# module-mcu.net
KiCad netlist of a schematic drawn in EAGLE
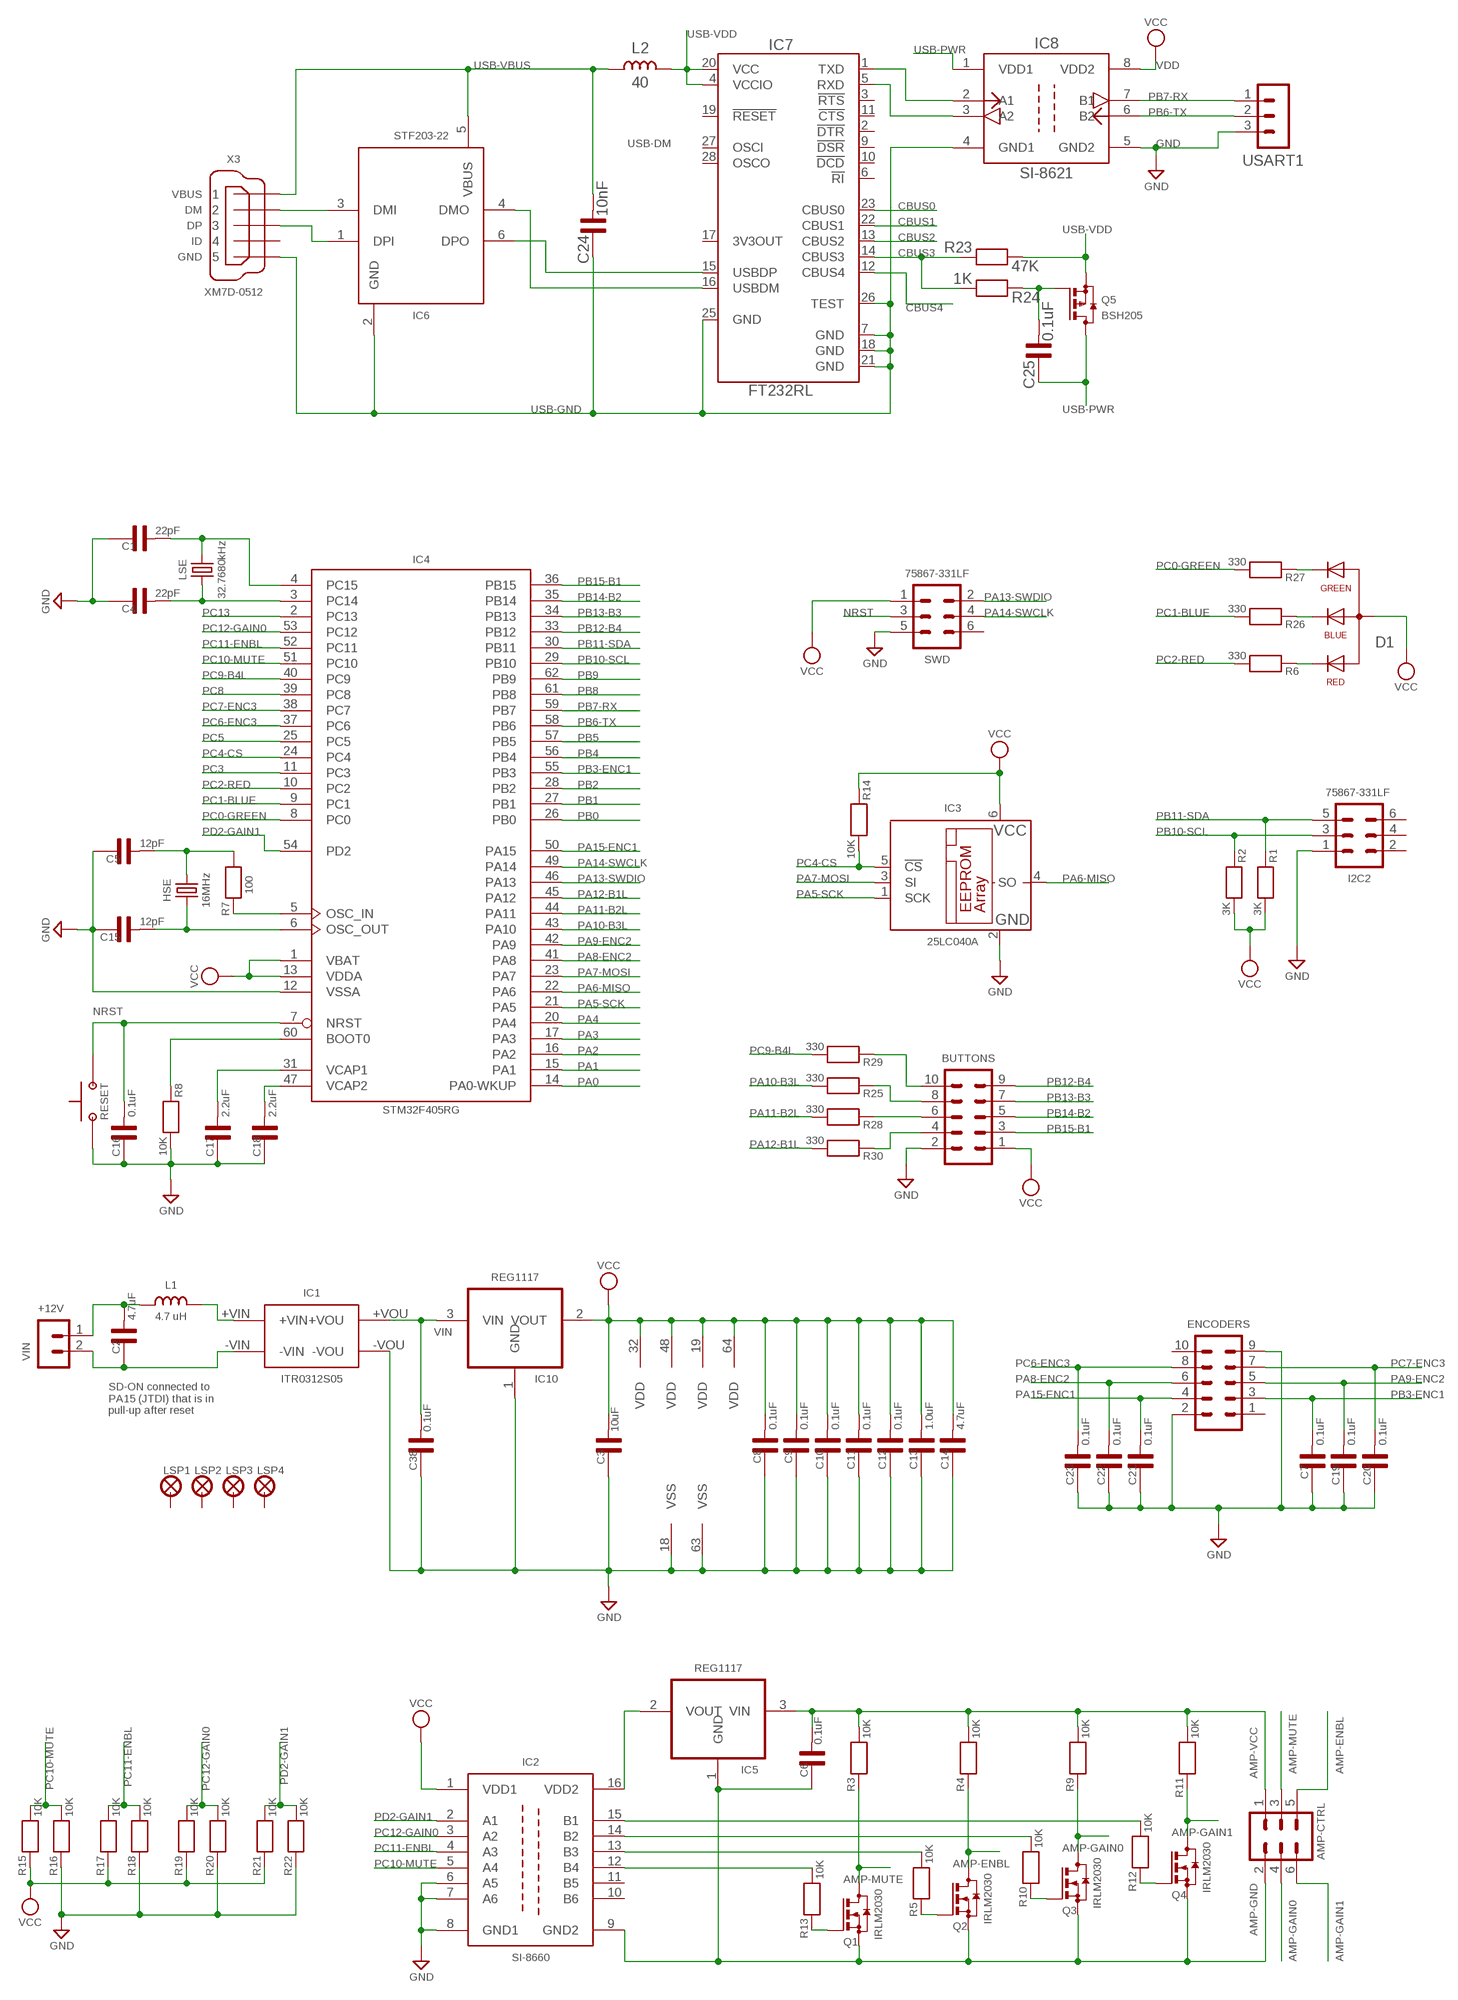
[diagram p0: schematic, sheet 1]

(export (version "E")
  (design (tool "Eeschema 10.0.6"))
  (components
    (comp (ref "AMP-CTRL")
      (value "MA03-2PL")
      (footprint "eagle-import:MA03-2")
      (libsource (lib "eagle-import") (part "MA03-2PL"))
    )
    (comp (ref "BUTTONS")
      (value "MA05-2")
      (footprint "eagle-import:MA05-2")
      (libsource (lib "eagle-import") (part "MA05-2"))
    )
    (comp (ref "C1")
      (value "22pF")
      (footprint "eagle-import:C0805")
      (libsource (lib "eagle-import") (part "C-US0805"))
    )
    (comp (ref "C2")
      (value "4.7uF")
      (footprint "eagle-import:C1206")
      (libsource (lib "eagle-import") (part "C-US1206"))
    )
    (comp (ref "C3")
      (value "10uF")
      (footprint "eagle-import:C0805")
      (libsource (lib "eagle-import") (part "C-US0805"))
    )
    (comp (ref "C4")
      (value "22pF")
      (footprint "eagle-import:C0805")
      (libsource (lib "eagle-import") (part "C-US0805"))
    )
    (comp (ref "C5")
      (value "12pF")
      (footprint "eagle-import:C0805")
      (libsource (lib "eagle-import") (part "C-US0805"))
    )
    (comp (ref "C6")
      (value "0.1uF")
      (footprint "eagle-import:C0805")
      (libsource (lib "eagle-import") (part "C-US0805"))
    )
    (comp (ref "C7")
      (value "0.1uF")
      (footprint "eagle-import:C0805")
      (libsource (lib "eagle-import") (part "C-US0805"))
    )
    (comp (ref "C8")
      (value "0.1uF")
      (footprint "eagle-import:C0805")
      (libsource (lib "eagle-import") (part "C-US0805"))
    )
    (comp (ref "C9")
      (value "0.1uF")
      (footprint "eagle-import:C0805")
      (libsource (lib "eagle-import") (part "C-US0805"))
    )
    (comp (ref "C10")
      (value "0.1uF")
      (footprint "eagle-import:C0805")
      (libsource (lib "eagle-import") (part "C-US0805"))
    )
    (comp (ref "C11")
      (value "0.1uF")
      (footprint "eagle-import:C0805")
      (libsource (lib "eagle-import") (part "C-US0805"))
    )
    (comp (ref "C12")
      (value "0.1uF")
      (footprint "eagle-import:C0805")
      (libsource (lib "eagle-import") (part "C-US0805"))
    )
    (comp (ref "C13")
      (value "1.0uF")
      (footprint "eagle-import:C0805")
      (libsource (lib "eagle-import") (part "C-US0805"))
    )
    (comp (ref "C14")
      (value "4.7uF")
      (footprint "eagle-import:C0805")
      (libsource (lib "eagle-import") (part "C-US0805"))
    )
    (comp (ref "C15")
      (value "12pF")
      (footprint "eagle-import:C0805")
      (libsource (lib "eagle-import") (part "C-US0805"))
    )
    (comp (ref "C16")
      (value "0.1uF")
      (footprint "eagle-import:C0805")
      (libsource (lib "eagle-import") (part "C-US0805"))
    )
    (comp (ref "C17")
      (value "2.2uF")
      (footprint "eagle-import:C0805")
      (libsource (lib "eagle-import") (part "C-US0805"))
    )
    (comp (ref "C18")
      (value "2.2uF")
      (footprint "eagle-import:C0805")
      (libsource (lib "eagle-import") (part "C-US0805"))
    )
    (comp (ref "C19")
      (value "0.1uF")
      (footprint "eagle-import:C0805")
      (libsource (lib "eagle-import") (part "C-US0805"))
    )
    (comp (ref "C20")
      (value "0.1uF")
      (footprint "eagle-import:C0805")
      (libsource (lib "eagle-import") (part "C-US0805"))
    )
    (comp (ref "C21")
      (value "0.1uF")
      (footprint "eagle-import:C0805")
      (libsource (lib "eagle-import") (part "C-US0805"))
    )
    (comp (ref "C22")
      (value "0.1uF")
      (footprint "eagle-import:C0805")
      (libsource (lib "eagle-import") (part "C-US0805"))
    )
    (comp (ref "C23")
      (value "0.1uF")
      (footprint "eagle-import:C0805")
      (libsource (lib "eagle-import") (part "C-US0805"))
    )
    (comp (ref "C24")
      (value "10nF")
      (footprint "eagle-import:C0805")
      (libsource (lib "eagle-import") (part "C-US0805"))
    )
    (comp (ref "C25")
      (value "0.1uF")
      (footprint "eagle-import:C0805")
      (libsource (lib "eagle-import") (part "C-US0805"))
    )
    (comp (ref "C38")
      (value "0.1uF")
      (footprint "eagle-import:C0805")
      (libsource (lib "eagle-import") (part "C-US0805"))
    )
    (comp (ref "D1")
      (value "RGB-LED3X1MM")
      (footprint "eagle-import:RGB-LED-SMD-3X1")
      (libsource (lib "eagle-import") (part "RGB-LED3X1MM"))
    )
    (comp (ref "ENCODERS")
      (value "MA05-2")
      (footprint "eagle-import:MA05-2")
      (libsource (lib "eagle-import") (part "MA05-2"))
    )
    (comp (ref "HSE")
      (value "16MHz")
      (footprint "eagle-import:Q-HC-46X")
      (libsource (lib "eagle-import") (part "Q-HSEHC-46X"))
    )
    (comp (ref "I2C2")
      (value "75867-331LF")
      (footprint "eagle-import:MA03-2")
      (libsource (lib "eagle-import") (part "MA03-2PL"))
    )
    (comp (ref "IC1")
      (value "ITR0312S05")
      (footprint "eagle-import:ITR0312S05")
      (libsource (lib "eagle-import") (part "ITR0312S05"))
    )
    (comp (ref "IC2")
      (value "SI-8660")
      (footprint "eagle-import:SO16")
      (libsource (lib "eagle-import") (part "SI-8660"))
    )
    (comp (ref "IC3")
      (value "25LC040A")
      (footprint "eagle-import:SOT23-6")
      (libsource (lib "eagle-import") (part "25LC040A"))
    )
    (comp (ref "IC4")
      (value "STM32F405RG")
      (footprint "eagle-import:LQFP64")
      (libsource (lib "eagle-import") (part "STM32F405RTG"))
    )
    (comp (ref "IC5")
      (value "REG1117")
      (footprint "eagle-import:SOT223")
      (libsource (lib "eagle-import") (part "REG1117"))
    )
    (comp (ref "IC6")
      (value "STF203-22")
      (footprint "eagle-import:SC70-6")
      (libsource (lib "eagle-import") (part "STF203-22"))
    )
    (comp (ref "IC7")
      (value "FT232RL")
      (footprint "eagle-import:SSOP28")
      (libsource (lib "eagle-import") (part "FT232RL"))
    )
    (comp (ref "IC8")
      (value "SI-8621")
      (footprint "eagle-import:SOIC-8")
      (libsource (lib "eagle-import") (part "SI-8621"))
    )
    (comp (ref "IC10")
      (value "REG1117")
      (footprint "eagle-import:SOT223")
      (libsource (lib "eagle-import") (part "REG1117"))
    )
    (comp (ref "L1")
      (value "4.7 uH")
      (footprint "eagle-import:L0805")
      (libsource (lib "eagle-import") (part "L-USL0805"))
    )
    (comp (ref "L2")
      (value "40")
      (footprint "eagle-import:L0805")
      (libsource (lib "eagle-import") (part "L-USL0805"))
    )
    (comp (ref "LSE")
      (value "32.7680kHz")
      (footprint "eagle-import:Q-CM7V-T1A")
      (libsource (lib "eagle-import") (part "Q-LSECM7V-T1A"))
    )
    (comp (ref "LSP1")
      (value "LSP27")
      (footprint "eagle-import:LSP27")
      (libsource (lib "eagle-import") (part "LSP27"))
    )
    (comp (ref "LSP2")
      (value "LSP27")
      (footprint "eagle-import:LSP27")
      (libsource (lib "eagle-import") (part "LSP27"))
    )
    (comp (ref "LSP3")
      (value "LSP27")
      (footprint "eagle-import:LSP27")
      (libsource (lib "eagle-import") (part "LSP27"))
    )
    (comp (ref "LSP4")
      (value "LSP27")
      (footprint "eagle-import:LSP27")
      (libsource (lib "eagle-import") (part "LSP27"))
    )
    (comp (ref "Q1")
      (value "IRLM2030")
      (footprint "eagle-import:SOT23")
      (libsource (lib "eagle-import") (part "BSS123"))
    )
    (comp (ref "Q2")
      (value "IRLM2030")
      (footprint "eagle-import:SOT23")
      (libsource (lib "eagle-import") (part "BSS123"))
    )
    (comp (ref "Q3")
      (value "IRLM2030")
      (footprint "eagle-import:SOT23")
      (libsource (lib "eagle-import") (part "BSS123"))
    )
    (comp (ref "Q4")
      (value "IRLM2030")
      (footprint "eagle-import:SOT23")
      (libsource (lib "eagle-import") (part "BSS123"))
    )
    (comp (ref "Q5")
      (value "BSH205")
      (footprint "eagle-import:SOT23")
      (libsource (lib "eagle-import") (part "BSH205G2R"))
    )
    (comp (ref "R1")
      (value "3K")
      (footprint "eagle-import:R0805")
      (libsource (lib "eagle-import") (part "R-US0805"))
    )
    (comp (ref "R2")
      (value "3K")
      (footprint "eagle-import:R0805")
      (libsource (lib "eagle-import") (part "R-US0805"))
    )
    (comp (ref "R3")
      (value "10K")
      (footprint "eagle-import:R0805")
      (libsource (lib "eagle-import") (part "R-US0805"))
    )
    (comp (ref "R4")
      (value "10K")
      (footprint "eagle-import:R0805")
      (libsource (lib "eagle-import") (part "R-US0805"))
    )
    (comp (ref "R5")
      (value "10K")
      (footprint "eagle-import:R0805")
      (libsource (lib "eagle-import") (part "R-US0805"))
    )
    (comp (ref "R6")
      (value "330")
      (footprint "eagle-import:R0805")
      (libsource (lib "eagle-import") (part "R-US0805"))
    )
    (comp (ref "R7")
      (value "100")
      (footprint "eagle-import:R0805")
      (libsource (lib "eagle-import") (part "R-US0805"))
    )
    (comp (ref "R8")
      (value "10K")
      (footprint "eagle-import:R0805")
      (libsource (lib "eagle-import") (part "R-US0805"))
    )
    (comp (ref "R9")
      (value "10K")
      (footprint "eagle-import:R0805")
      (libsource (lib "eagle-import") (part "R-US0805"))
    )
    (comp (ref "R10")
      (value "10K")
      (footprint "eagle-import:R0805")
      (libsource (lib "eagle-import") (part "R-US0805"))
    )
    (comp (ref "R11")
      (value "10K")
      (footprint "eagle-import:R0805")
      (libsource (lib "eagle-import") (part "R-US0805"))
    )
    (comp (ref "R12")
      (value "10K")
      (footprint "eagle-import:R0805")
      (libsource (lib "eagle-import") (part "R-US0805"))
    )
    (comp (ref "R13")
      (value "10K")
      (footprint "eagle-import:R0805")
      (libsource (lib "eagle-import") (part "R-US0805"))
    )
    (comp (ref "R14")
      (value "10K")
      (footprint "eagle-import:R0805")
      (libsource (lib "eagle-import") (part "R-US0805"))
    )
    (comp (ref "R15")
      (value "10K")
      (footprint "eagle-import:R0805")
      (libsource (lib "eagle-import") (part "R-US0805"))
    )
    (comp (ref "R16")
      (value "10K")
      (footprint "eagle-import:R0805")
      (libsource (lib "eagle-import") (part "R-US0805"))
    )
    (comp (ref "R17")
      (value "10K")
      (footprint "eagle-import:R0805")
      (libsource (lib "eagle-import") (part "R-US0805"))
    )
    (comp (ref "R18")
      (value "10K")
      (footprint "eagle-import:R0805")
      (libsource (lib "eagle-import") (part "R-US0805"))
    )
    (comp (ref "R19")
      (value "10K")
      (footprint "eagle-import:R0805")
      (libsource (lib "eagle-import") (part "R-US0805"))
    )
    (comp (ref "R20")
      (value "10K")
      (footprint "eagle-import:R0805")
      (libsource (lib "eagle-import") (part "R-US0805"))
    )
    (comp (ref "R21")
      (value "10K")
      (footprint "eagle-import:R0805")
      (libsource (lib "eagle-import") (part "R-US0805"))
    )
    (comp (ref "R22")
      (value "10K")
      (footprint "eagle-import:R0805")
      (libsource (lib "eagle-import") (part "R-US0805"))
    )
    (comp (ref "R23")
      (value "47K")
      (footprint "eagle-import:R0805")
      (libsource (lib "eagle-import") (part "R-US0805"))
    )
    (comp (ref "R24")
      (value "1K")
      (footprint "eagle-import:R0805")
      (libsource (lib "eagle-import") (part "R-US0805"))
    )
    (comp (ref "R25")
      (value "330")
      (footprint "eagle-import:R0805")
      (libsource (lib "eagle-import") (part "R-US0805"))
    )
    (comp (ref "R26")
      (value "330")
      (footprint "eagle-import:R0805")
      (libsource (lib "eagle-import") (part "R-US0805"))
    )
    (comp (ref "R27")
      (value "330")
      (footprint "eagle-import:R0805")
      (libsource (lib "eagle-import") (part "R-US0805"))
    )
    (comp (ref "R28")
      (value "330")
      (footprint "eagle-import:R0805")
      (libsource (lib "eagle-import") (part "R-US0805"))
    )
    (comp (ref "R29")
      (value "330")
      (footprint "eagle-import:R0805")
      (libsource (lib "eagle-import") (part "R-US0805"))
    )
    (comp (ref "R30")
      (value "330")
      (footprint "eagle-import:R0805")
      (libsource (lib "eagle-import") (part "R-US0805"))
    )
    (comp (ref "RESET")
      (value "BUTTON-FSM14JRT")
      (footprint "eagle-import:BUTTON-FSM14JRT")
      (libsource (lib "eagle-import") (part "BUTTON-FSM14JRT"))
    )
    (comp (ref "SWD")
      (value "75867-331LF")
      (footprint "eagle-import:MA03-2-BLUE")
      (libsource (lib "eagle-import") (part "MA03-2BLUE"))
    )
    (comp (ref "USART1")
      (value "MA03-1PL")
      (footprint "eagle-import:MA03-1")
      (libsource (lib "eagle-import") (part "MA03-1PL"))
    )
    (comp (ref "VIN")
      (value "MA02-1GREEN")
      (footprint "eagle-import:MA02-1-GREEN")
      (libsource (lib "eagle-import") (part "MA02-1GREEN"))
    )
    (comp (ref "X3")
      (value "XM7D-0512")
      (footprint "eagle-import:XM7D-0512")
      (libsource (lib "eagle-import") (part "MINI-USB-5-DPI"))
    )
  )
  (nets
    (net (code "2") (name "/AMP-ENBL") (class "Default")
      (node (ref "AMP-CTRL") (pin "5") (pinfunction "5_5") (pintype "passive"))
      (node (ref "Q2") (pin "3") (pinfunction "D_3") (pintype "passive"))
      (node (ref "R4") (pin "1") (pinfunction "1_1") (pintype "passive"))
    )
    (net (code "3") (name "/AMP-GAIN0") (class "Default")
      (node (ref "AMP-CTRL") (pin "4") (pinfunction "4_4") (pintype "passive"))
      (node (ref "Q3") (pin "3") (pinfunction "D_3") (pintype "passive"))
      (node (ref "R9") (pin "1") (pinfunction "1_1") (pintype "passive"))
    )
    (net (code "4") (name "/AMP-GAIN1") (class "Default")
      (node (ref "AMP-CTRL") (pin "6") (pinfunction "6_6") (pintype "passive"))
      (node (ref "Q4") (pin "3") (pinfunction "D_3") (pintype "passive"))
      (node (ref "R11") (pin "1") (pinfunction "1_1") (pintype "passive"))
    )
    (net (code "5") (name "/AMP-GND") (class "Default")
      (node (ref "AMP-CTRL") (pin "2") (pinfunction "2_2") (pintype "passive"))
      (node (ref "C6") (pin "1") (pinfunction "1_1") (pintype "passive"))
      (node (ref "IC2") (pin "9") (pinfunction "GND2_9") (pintype "bidirectional"))
      (node (ref "IC5") (pin "1") (pinfunction "GND_1") (pintype "power_in"))
      (node (ref "Q1") (pin "2") (pinfunction "S_2") (pintype "passive"))
      (node (ref "Q2") (pin "2") (pinfunction "S_2") (pintype "passive"))
      (node (ref "Q3") (pin "2") (pinfunction "S_2") (pintype "passive"))
      (node (ref "Q4") (pin "2") (pinfunction "S_2") (pintype "passive"))
    )
    (net (code "6") (name "/AMP-MUTE") (class "Default")
      (node (ref "AMP-CTRL") (pin "3") (pinfunction "3_3") (pintype "passive"))
      (node (ref "Q1") (pin "3") (pinfunction "D_3") (pintype "passive"))
      (node (ref "R3") (pin "1") (pinfunction "1_1") (pintype "passive"))
    )
    (net (code "7") (name "/AMP-VCC") (class "Default")
      (node (ref "AMP-CTRL") (pin "1") (pinfunction "1_1") (pintype "passive"))
      (node (ref "C6") (pin "2") (pinfunction "2_2") (pintype "passive"))
      (node (ref "IC5") (pin "3") (pinfunction "VIN_3") (pintype "input"))
      (node (ref "R11") (pin "2") (pinfunction "2_2") (pintype "passive"))
      (node (ref "R3") (pin "2") (pinfunction "2_2") (pintype "passive"))
      (node (ref "R4") (pin "2") (pinfunction "2_2") (pintype "passive"))
      (node (ref "R9") (pin "2") (pinfunction "2_2") (pintype "passive"))
    )
    (net (code "8") (name "/CBUS0") (class "Default")
      (node (ref "IC7") (pin "23") (pinfunction "CBUS0_23") (pintype "bidirectional"))
    )
    (net (code "9") (name "/CBUS1") (class "Default")
      (node (ref "IC7") (pin "22") (pinfunction "CBUS1_22") (pintype "bidirectional"))
    )
    (net (code "10") (name "/CBUS2") (class "Default")
      (node (ref "IC7") (pin "13") (pinfunction "CBUS2_13") (pintype "bidirectional"))
    )
    (net (code "11") (name "/CBUS3") (class "Default")
      (node (ref "IC7") (pin "14") (pinfunction "CBUS3_14") (pintype "bidirectional"))
      (node (ref "R23") (pin "1") (pinfunction "1_1") (pintype "passive"))
      (node (ref "R24") (pin "2") (pinfunction "2_2") (pintype "passive"))
    )
    (net (code "12") (name "/CBUS4") (class "Default")
      (node (ref "IC7") (pin "12") (pinfunction "CBUS4_12") (pintype "bidirectional"))
    )
    (net (code "13") (name "/NRST") (class "Default")
      (node (ref "C16") (pin "2") (pinfunction "2_2") (pintype "passive"))
      (node (ref "IC4") (pin "7") (pinfunction "NRST_7") (pintype "bidirectional"))
      (node (ref "RESET") (pin "P$2") (pinfunction "2_P$2") (pintype "bidirectional"))
      (node (ref "SWD") (pin "3") (pinfunction "3_3") (pintype "passive"))
    )
    (net (code "14") (name "/PA0") (class "Default")
      (node (ref "IC4") (pin "14") (pinfunction "PA0-WKUP_14") (pintype "bidirectional"))
    )
    (net (code "15") (name "/PA1") (class "Default")
      (node (ref "IC4") (pin "15") (pinfunction "PA1_15") (pintype "bidirectional"))
    )
    (net (code "16") (name "/PA2") (class "Default")
      (node (ref "IC4") (pin "16") (pinfunction "PA2_16") (pintype "bidirectional"))
    )
    (net (code "17") (name "/PA3") (class "Default")
      (node (ref "IC4") (pin "17") (pinfunction "PA3_17") (pintype "bidirectional"))
    )
    (net (code "18") (name "/PA4") (class "Default")
      (node (ref "IC4") (pin "20") (pinfunction "PA4_20") (pintype "bidirectional"))
    )
    (net (code "19") (name "/PA5-SCK") (class "Default")
      (node (ref "IC3") (pin "1") (pinfunction "SCK_1") (pintype "input"))
      (node (ref "IC4") (pin "21") (pinfunction "PA5_21") (pintype "bidirectional"))
    )
    (net (code "20") (name "/PA6-MISO") (class "Default")
      (node (ref "IC3") (pin "4") (pinfunction "SO_4") (pintype "bidirectional"))
      (node (ref "IC4") (pin "22") (pinfunction "PA6_22") (pintype "bidirectional"))
    )
    (net (code "21") (name "/PA7-MOSI") (class "Default")
      (node (ref "IC3") (pin "3") (pinfunction "SI_3") (pintype "input"))
      (node (ref "IC4") (pin "23") (pinfunction "PA7_23") (pintype "bidirectional"))
    )
    (net (code "22") (name "/PA8-ENC2") (class "Default")
      (node (ref "C22") (pin "2") (pinfunction "2_2") (pintype "passive"))
      (node (ref "ENCODERS") (pin "6") (pinfunction "6_6") (pintype "passive"))
      (node (ref "IC4") (pin "41") (pinfunction "PA8_41") (pintype "bidirectional"))
    )
    (net (code "23") (name "/PA9-ENC2") (class "Default")
      (node (ref "C19") (pin "2") (pinfunction "2_2") (pintype "passive"))
      (node (ref "ENCODERS") (pin "5") (pinfunction "5_5") (pintype "passive"))
      (node (ref "IC4") (pin "42") (pinfunction "PA9_42") (pintype "bidirectional"))
    )
    (net (code "24") (name "/PA10-B3L") (class "Default")
      (node (ref "IC4") (pin "43") (pinfunction "PA10_43") (pintype "bidirectional"))
      (node (ref "R25") (pin "2") (pinfunction "2_2") (pintype "passive"))
    )
    (net (code "25") (name "/PA11-B2L") (class "Default")
      (node (ref "IC4") (pin "44") (pinfunction "PA11_44") (pintype "bidirectional"))
      (node (ref "R28") (pin "2") (pinfunction "2_2") (pintype "passive"))
    )
    (net (code "26") (name "/PA12-B1L") (class "Default")
      (node (ref "IC4") (pin "45") (pinfunction "PA12_45") (pintype "bidirectional"))
      (node (ref "R30") (pin "2") (pinfunction "2_2") (pintype "passive"))
    )
    (net (code "27") (name "/PA13-SWDIO") (class "Default")
      (node (ref "IC4") (pin "46") (pinfunction "PA13_46") (pintype "bidirectional"))
      (node (ref "SWD") (pin "2") (pinfunction "2_2") (pintype "passive"))
    )
    (net (code "28") (name "/PA14-SWCLK") (class "Default")
      (node (ref "IC4") (pin "49") (pinfunction "PA14_49") (pintype "bidirectional"))
      (node (ref "SWD") (pin "4") (pinfunction "4_4") (pintype "passive"))
    )
    (net (code "29") (name "/PA15-ENC1") (class "Default")
      (node (ref "C21") (pin "2") (pinfunction "2_2") (pintype "passive"))
      (node (ref "ENCODERS") (pin "4") (pinfunction "4_4") (pintype "passive"))
      (node (ref "IC4") (pin "50") (pinfunction "PA15_50") (pintype "bidirectional"))
    )
    (net (code "30") (name "/PB0") (class "Default")
      (node (ref "IC4") (pin "26") (pinfunction "PB0_26") (pintype "bidirectional"))
    )
    (net (code "31") (name "/PB1") (class "Default")
      (node (ref "IC4") (pin "27") (pinfunction "PB1_27") (pintype "bidirectional"))
    )
    (net (code "32") (name "/PB2") (class "Default")
      (node (ref "IC4") (pin "28") (pinfunction "PB2_28") (pintype "bidirectional"))
    )
    (net (code "33") (name "/PB3-ENC1") (class "Default")
      (node (ref "C7") (pin "2") (pinfunction "2_2") (pintype "passive"))
      (node (ref "ENCODERS") (pin "3") (pinfunction "3_3") (pintype "passive"))
      (node (ref "IC4") (pin "55") (pinfunction "PB3_55") (pintype "bidirectional"))
    )
    (net (code "34") (name "/PB4") (class "Default")
      (node (ref "IC4") (pin "56") (pinfunction "PB4_56") (pintype "bidirectional"))
    )
    (net (code "35") (name "/PB5") (class "Default")
      (node (ref "IC4") (pin "57") (pinfunction "PB5_57") (pintype "bidirectional"))
    )
    (net (code "36") (name "/PB6-TX") (class "Default")
      (node (ref "IC4") (pin "58") (pinfunction "PB6_58") (pintype "bidirectional"))
      (node (ref "IC8") (pin "6") (pinfunction "B2_6") (pintype "bidirectional"))
      (node (ref "USART1") (pin "2") (pinfunction "2_2") (pintype "passive"))
    )
    (net (code "37") (name "/PB7-RX") (class "Default")
      (node (ref "IC4") (pin "59") (pinfunction "PB7_59") (pintype "bidirectional"))
      (node (ref "IC8") (pin "7") (pinfunction "B1_7") (pintype "bidirectional"))
      (node (ref "USART1") (pin "1") (pinfunction "1_1") (pintype "passive"))
    )
    (net (code "38") (name "/PB8") (class "Default")
      (node (ref "IC4") (pin "61") (pinfunction "PB8_61") (pintype "bidirectional"))
    )
    (net (code "39") (name "/PB9") (class "Default")
      (node (ref "IC4") (pin "62") (pinfunction "PB9_62") (pintype "bidirectional"))
    )
    (net (code "40") (name "/PB10-SCL") (class "Default")
      (node (ref "I2C2") (pin "3") (pinfunction "3_3") (pintype "passive"))
      (node (ref "IC4") (pin "29") (pinfunction "PB10_29") (pintype "bidirectional"))
      (node (ref "R2") (pin "1") (pinfunction "1_1") (pintype "passive"))
    )
    (net (code "41") (name "/PB11-SDA") (class "Default")
      (node (ref "I2C2") (pin "5") (pinfunction "5_5") (pintype "passive"))
      (node (ref "IC4") (pin "30") (pinfunction "PB11_30") (pintype "bidirectional"))
      (node (ref "R1") (pin "1") (pinfunction "1_1") (pintype "passive"))
    )
    (net (code "42") (name "/PB12-B4") (class "Default")
      (node (ref "BUTTONS") (pin "9") (pinfunction "9_9") (pintype "passive"))
      (node (ref "IC4") (pin "33") (pinfunction "PB12_33") (pintype "bidirectional"))
    )
    (net (code "43") (name "/PB13-B3") (class "Default")
      (node (ref "BUTTONS") (pin "7") (pinfunction "7_7") (pintype "passive"))
      (node (ref "IC4") (pin "34") (pinfunction "PB13_34") (pintype "bidirectional"))
    )
    (net (code "44") (name "/PB14-B2") (class "Default")
      (node (ref "BUTTONS") (pin "5") (pinfunction "5_5") (pintype "passive"))
      (node (ref "IC4") (pin "35") (pinfunction "PB14_35") (pintype "bidirectional"))
    )
    (net (code "45") (name "/PB15-B1") (class "Default")
      (node (ref "BUTTONS") (pin "3") (pinfunction "3_3") (pintype "passive"))
      (node (ref "IC4") (pin "36") (pinfunction "PB15_36") (pintype "bidirectional"))
    )
    (net (code "46") (name "/PC0-GREEN") (class "Default")
      (node (ref "IC4") (pin "8") (pinfunction "PC0_8") (pintype "bidirectional"))
      (node (ref "R27") (pin "2") (pinfunction "2_2") (pintype "passive"))
    )
    (net (code "47") (name "/PC1-BLUE") (class "Default")
      (node (ref "IC4") (pin "9") (pinfunction "PC1_9") (pintype "bidirectional"))
      (node (ref "R26") (pin "2") (pinfunction "2_2") (pintype "passive"))
    )
    (net (code "48") (name "/PC2-RED") (class "Default")
      (node (ref "IC4") (pin "10") (pinfunction "PC2_10") (pintype "bidirectional"))
      (node (ref "R6") (pin "2") (pinfunction "2_2") (pintype "passive"))
    )
    (net (code "49") (name "/PC3") (class "Default")
      (node (ref "IC4") (pin "11") (pinfunction "PC3_11") (pintype "bidirectional"))
    )
    (net (code "50") (name "/PC4-CS") (class "Default")
      (node (ref "IC3") (pin "5") (pinfunction "~{CS}_5") (pintype "input"))
      (node (ref "IC4") (pin "24") (pinfunction "PC4_24") (pintype "bidirectional"))
      (node (ref "R14") (pin "2") (pinfunction "2_2") (pintype "passive"))
    )
    (net (code "51") (name "/PC5") (class "Default")
      (node (ref "IC4") (pin "25") (pinfunction "PC5_25") (pintype "bidirectional"))
    )
    (net (code "52") (name "/PC6-ENC3") (class "Default")
      (node (ref "C23") (pin "2") (pinfunction "2_2") (pintype "passive"))
      (node (ref "ENCODERS") (pin "8") (pinfunction "8_8") (pintype "passive"))
      (node (ref "IC4") (pin "37") (pinfunction "PC6_37") (pintype "bidirectional"))
    )
    (net (code "53") (name "/PC7-ENC3") (class "Default")
      (node (ref "C20") (pin "2") (pinfunction "2_2") (pintype "passive"))
      (node (ref "ENCODERS") (pin "7") (pinfunction "7_7") (pintype "passive"))
      (node (ref "IC4") (pin "38") (pinfunction "PC7_38") (pintype "bidirectional"))
    )
    (net (code "54") (name "/PC8") (class "Default")
      (node (ref "IC4") (pin "39") (pinfunction "PC8_39") (pintype "bidirectional"))
    )
    (net (code "55") (name "/PC9-B4L") (class "Default")
      (node (ref "IC4") (pin "40") (pinfunction "PC9_40") (pintype "bidirectional"))
      (node (ref "R29") (pin "2") (pinfunction "2_2") (pintype "passive"))
    )
    (net (code "56") (name "/PC10-MUTE") (class "Default")
      (node (ref "IC2") (pin "5") (pinfunction "A4_5") (pintype "bidirectional"))
      (node (ref "IC4") (pin "51") (pinfunction "PC10_51") (pintype "bidirectional"))
      (node (ref "R15") (pin "2") (pinfunction "2_2") (pintype "passive"))
      (node (ref "R16") (pin "2") (pinfunction "2_2") (pintype "passive"))
    )
    (net (code "57") (name "/PC11-ENBL") (class "Default")
      (node (ref "IC2") (pin "4") (pinfunction "A3_4") (pintype "bidirectional"))
      (node (ref "IC4") (pin "52") (pinfunction "PC11_52") (pintype "bidirectional"))
      (node (ref "R17") (pin "2") (pinfunction "2_2") (pintype "passive"))
      (node (ref "R18") (pin "2") (pinfunction "2_2") (pintype "passive"))
    )
    (net (code "58") (name "/PC12-GAIN0") (class "Default")
      (node (ref "IC2") (pin "3") (pinfunction "A2_3") (pintype "bidirectional"))
      (node (ref "IC4") (pin "53") (pinfunction "PC12_53") (pintype "bidirectional"))
      (node (ref "R19") (pin "2") (pinfunction "2_2") (pintype "passive"))
      (node (ref "R20") (pin "2") (pinfunction "2_2") (pintype "passive"))
    )
    (net (code "59") (name "/PC13") (class "Default")
      (node (ref "IC4") (pin "2") (pinfunction "PC13_2") (pintype "bidirectional"))
    )
    (net (code "60") (name "/PD2-GAIN1") (class "Default")
      (node (ref "IC2") (pin "2") (pinfunction "A1_2") (pintype "bidirectional"))
      (node (ref "IC4") (pin "54") (pinfunction "PD2_54") (pintype "bidirectional"))
      (node (ref "R21") (pin "2") (pinfunction "2_2") (pintype "passive"))
      (node (ref "R22") (pin "2") (pinfunction "2_2") (pintype "passive"))
    )
    (net (code "61") (name "/USB-DM") (class "Default")
      (node (ref "IC6") (pin "4") (pinfunction "DMO_4") (pintype "bidirectional"))
      (node (ref "IC7") (pin "16") (pinfunction "USBDM_16") (pintype "bidirectional"))
    )
    (net (code "62") (name "/USB-GND") (class "Default")
      (node (ref "C24") (pin "1") (pinfunction "1_1") (pintype "passive"))
      (node (ref "IC6") (pin "2") (pinfunction "GND_2") (pintype "bidirectional"))
      (node (ref "IC7") (pin "18") (pinfunction "GND_18") (pintype "power_in"))
      (node (ref "IC7") (pin "21") (pinfunction "GND_21") (pintype "power_in"))
      (node (ref "IC7") (pin "25") (pinfunction "GND_25") (pintype "power_in"))
      (node (ref "IC7") (pin "26") (pinfunction "TEST_26") (pintype "input"))
      (node (ref "IC7") (pin "7") (pinfunction "GND_7") (pintype "power_in"))
      (node (ref "IC8") (pin "4") (pinfunction "GND1_4") (pintype "bidirectional"))
      (node (ref "X3") (pin "5") (pinfunction "5_5") (pintype "passive"))
    )
    (net (code "63") (name "/USB-PWR") (class "Default")
      (node (ref "C25") (pin "1") (pinfunction "1_1") (pintype "passive"))
      (node (ref "IC8") (pin "1") (pinfunction "VDD1_1") (pintype "bidirectional"))
      (node (ref "Q5") (pin "3") (pinfunction "D_3") (pintype "passive"))
    )
    (net (code "64") (name "/USB-VBUS") (class "Default")
      (node (ref "C24") (pin "2") (pinfunction "2_2") (pintype "passive"))
      (node (ref "IC6") (pin "5") (pinfunction "VBUS_5") (pintype "bidirectional"))
      (node (ref "L2") (pin "1") (pinfunction "1_1") (pintype "passive"))
      (node (ref "X3") (pin "1") (pinfunction "1_1") (pintype "passive"))
    )
    (net (code "65") (name "/USB-VDD") (class "Default")
      (node (ref "IC7") (pin "20") (pinfunction "VCC_20") (pintype "power_in"))
      (node (ref "IC7") (pin "4") (pinfunction "VCCIO_4") (pintype "power_in"))
      (node (ref "L2") (pin "2") (pinfunction "2_2") (pintype "passive"))
      (node (ref "Q5") (pin "2") (pinfunction "S_2") (pintype "passive"))
      (node (ref "R23") (pin "2") (pinfunction "2_2") (pintype "passive"))
    )
    (net (code "66") (name "/VIN") (class "Default")
      (node (ref "C38") (pin "2") (pinfunction "2_2") (pintype "passive"))
      (node (ref "IC1") (pin "+VOU") (pinfunction "+VOU_+VOU") (pintype "bidirectional"))
      (node (ref "IC10") (pin "3") (pinfunction "VIN_3") (pintype "input"))
    )
    (net (code "67") (name "GND") (class "Default")
      (node (ref "BUTTONS") (pin "2") (pinfunction "2_2") (pintype "passive"))
      (node (ref "C1") (pin "1") (pinfunction "1_1") (pintype "passive"))
      (node (ref "C10") (pin "1") (pinfunction "1_1") (pintype "passive"))
      (node (ref "C11") (pin "1") (pinfunction "1_1") (pintype "passive"))
      (node (ref "C12") (pin "1") (pinfunction "1_1") (pintype "passive"))
      (node (ref "C13") (pin "1") (pinfunction "1_1") (pintype "passive"))
      (node (ref "C14") (pin "1") (pinfunction "1_1") (pintype "passive"))
      (node (ref "C15") (pin "1") (pinfunction "1_1") (pintype "passive"))
      (node (ref "C16") (pin "1") (pinfunction "1_1") (pintype "passive"))
      (node (ref "C17") (pin "1") (pinfunction "1_1") (pintype "passive"))
      (node (ref "C18") (pin "1") (pinfunction "1_1") (pintype "passive"))
      (node (ref "C19") (pin "1") (pinfunction "1_1") (pintype "passive"))
      (node (ref "C20") (pin "1") (pinfunction "1_1") (pintype "passive"))
      (node (ref "C21") (pin "1") (pinfunction "1_1") (pintype "passive"))
      (node (ref "C22") (pin "1") (pinfunction "1_1") (pintype "passive"))
      (node (ref "C23") (pin "1") (pinfunction "1_1") (pintype "passive"))
      (node (ref "C3") (pin "1") (pinfunction "1_1") (pintype "passive"))
      (node (ref "C38") (pin "1") (pinfunction "1_1") (pintype "passive"))
      (node (ref "C4") (pin "1") (pinfunction "1_1") (pintype "passive"))
      (node (ref "C5") (pin "1") (pinfunction "1_1") (pintype "passive"))
      (node (ref "C7") (pin "1") (pinfunction "1_1") (pintype "passive"))
      (node (ref "C8") (pin "1") (pinfunction "1_1") (pintype "passive"))
      (node (ref "C9") (pin "1") (pinfunction "1_1") (pintype "passive"))
      (node (ref "ENCODERS") (pin "2") (pinfunction "2_2") (pintype "passive"))
      (node (ref "ENCODERS") (pin "9") (pinfunction "9_9") (pintype "passive"))
      (node (ref "I2C2") (pin "1") (pinfunction "1_1") (pintype "passive"))
      (node (ref "IC1") (pin "-VOU") (pinfunction "-VOU_-VOU") (pintype "bidirectional"))
      (node (ref "IC10") (pin "1") (pinfunction "GND_1") (pintype "power_in"))
      (node (ref "IC2") (pin "6") (pinfunction "A5_6") (pintype "bidirectional"))
      (node (ref "IC2") (pin "7") (pinfunction "A6_7") (pintype "bidirectional"))
      (node (ref "IC2") (pin "8") (pinfunction "GND1_8") (pintype "bidirectional"))
      (node (ref "IC3") (pin "2") (pinfunction "GND_2") (pintype "power_in"))
      (node (ref "IC4") (pin "12") (pinfunction "VSSA_12") (pintype "power_in"))
      (node (ref "IC4") (pin "18") (pinfunction "VSS_18") (pintype "power_in"))
      (node (ref "IC4") (pin "63") (pinfunction "VSS_63") (pintype "power_in"))
      (node (ref "IC8") (pin "5") (pinfunction "GND2_5") (pintype "bidirectional"))
      (node (ref "R16") (pin "1") (pinfunction "1_1") (pintype "passive"))
      (node (ref "R18") (pin "1") (pinfunction "1_1") (pintype "passive"))
      (node (ref "R20") (pin "1") (pinfunction "1_1") (pintype "passive"))
      (node (ref "R22") (pin "1") (pinfunction "1_1") (pintype "passive"))
      (node (ref "R8") (pin "2") (pinfunction "2_2") (pintype "passive"))
      (node (ref "RESET") (pin "P$1") (pinfunction "1_P$1") (pintype "bidirectional"))
      (node (ref "SWD") (pin "5") (pinfunction "5_5") (pintype "passive"))
      (node (ref "USART1") (pin "3") (pinfunction "3_3") (pintype "passive"))
    )
    (net (code "68") (name "Net-(BUTTONS-Pad4)") (class "Default")
      (node (ref "BUTTONS") (pin "4") (pinfunction "4_4") (pintype "passive"))
      (node (ref "R30") (pin "1") (pinfunction "1_1") (pintype "passive"))
    )
    (net (code "69") (name "Net-(BUTTONS-Pad6)") (class "Default")
      (node (ref "BUTTONS") (pin "6") (pinfunction "6_6") (pintype "passive"))
      (node (ref "R28") (pin "1") (pinfunction "1_1") (pintype "passive"))
    )
    (net (code "70") (name "Net-(BUTTONS-Pad8)") (class "Default")
      (node (ref "BUTTONS") (pin "8") (pinfunction "8_8") (pintype "passive"))
      (node (ref "R25") (pin "1") (pinfunction "1_1") (pintype "passive"))
    )
    (net (code "71") (name "Net-(BUTTONS-Pad10)") (class "Default")
      (node (ref "BUTTONS") (pin "10") (pinfunction "10_10") (pintype "passive"))
      (node (ref "R29") (pin "1") (pinfunction "1_1") (pintype "passive"))
    )
    (net (code "72") (name "Net-(C2-Pad1)") (class "Default")
      (node (ref "C2") (pin "1") (pinfunction "1_1") (pintype "passive"))
      (node (ref "IC1") (pin "-VIN") (pinfunction "-VIN_-VIN") (pintype "bidirectional"))
      (node (ref "VIN") (pin "2") (pinfunction "2_2") (pintype "passive"))
    )
    (net (code "73") (name "Net-(C2-Pad2)") (class "Default")
      (node (ref "C2") (pin "2") (pinfunction "2_2") (pintype "passive"))
      (node (ref "L1") (pin "1") (pinfunction "1_1") (pintype "passive"))
      (node (ref "VIN") (pin "1") (pinfunction "1_1") (pintype "passive"))
    )
    (net (code "74") (name "Net-(C5-Pad2)") (class "Default")
      (node (ref "C5") (pin "2") (pinfunction "2_2") (pintype "passive"))
      (node (ref "HSE") (pin "1") (pinfunction "1_1") (pintype "passive"))
      (node (ref "R7") (pin "2") (pinfunction "2_2") (pintype "passive"))
    )
    (net (code "75") (name "Net-(D1-AB)") (class "Default")
      (node (ref "D1") (pin "P$4") (pinfunction "AB_P$4") (pintype "passive"))
      (node (ref "R26") (pin "1") (pinfunction "1_1") (pintype "passive"))
    )
    (net (code "76") (name "Net-(D1-AG)") (class "Default")
      (node (ref "D1") (pin "P$3") (pinfunction "AG_P$3") (pintype "passive"))
      (node (ref "R27") (pin "1") (pinfunction "1_1") (pintype "passive"))
    )
    (net (code "77") (name "Net-(D1-AR)") (class "Default")
      (node (ref "D1") (pin "P$1") (pinfunction "AR_P$1") (pintype "passive"))
      (node (ref "R6") (pin "1") (pinfunction "1_1") (pintype "passive"))
    )
    (net (code "78") (name "Net-(IC1-Pad+VIN)") (class "Default")
      (node (ref "IC1") (pin "+VIN") (pinfunction "+VIN_+VIN") (pintype "bidirectional"))
      (node (ref "L1") (pin "2") (pinfunction "2_2") (pintype "passive"))
    )
    (net (code "79") (name "Net-(IC2-B1)") (class "Default")
      (node (ref "IC2") (pin "15") (pinfunction "B1_15") (pintype "bidirectional"))
      (node (ref "R12") (pin "2") (pinfunction "2_2") (pintype "passive"))
    )
    (net (code "80") (name "Net-(IC2-B2)") (class "Default")
      (node (ref "IC2") (pin "14") (pinfunction "B2_14") (pintype "bidirectional"))
      (node (ref "R10") (pin "2") (pinfunction "2_2") (pintype "passive"))
    )
    (net (code "81") (name "Net-(IC2-B3)") (class "Default")
      (node (ref "IC2") (pin "13") (pinfunction "B3_13") (pintype "bidirectional"))
      (node (ref "R5") (pin "2") (pinfunction "2_2") (pintype "passive"))
    )
    (net (code "82") (name "Net-(IC2-B4)") (class "Default")
      (node (ref "IC2") (pin "12") (pinfunction "B4_12") (pintype "bidirectional"))
      (node (ref "R13") (pin "2") (pinfunction "2_2") (pintype "passive"))
    )
    (net (code "83") (name "Net-(IC2-VDD2)") (class "Default")
      (node (ref "IC2") (pin "16") (pinfunction "VDD2_16") (pintype "bidirectional"))
      (node (ref "IC5") (pin "2") (pinfunction "VOUT_2") (pintype "output"))
    )
    (net (code "84") (name "Net-(IC4A-BOOT0)") (class "Default")
      (node (ref "IC4") (pin "60") (pinfunction "BOOT0_60") (pintype "input"))
      (node (ref "R8") (pin "1") (pinfunction "1_1") (pintype "passive"))
    )
    (net (code "85") (name "Net-(IC4A-OSC_IN)") (class "Default")
      (node (ref "IC4") (pin "5") (pinfunction "OSC_IN_5") (pintype "bidirectional"))
      (node (ref "R7") (pin "1") (pinfunction "1_1") (pintype "passive"))
    )
    (net (code "86") (name "Net-(IC4A-OSC_OUT)") (class "Default")
      (node (ref "C15") (pin "2") (pinfunction "2_2") (pintype "passive"))
      (node (ref "HSE") (pin "2") (pinfunction "2_2") (pintype "passive"))
      (node (ref "IC4") (pin "6") (pinfunction "OSC_OUT_6") (pintype "bidirectional"))
    )
    (net (code "87") (name "Net-(IC4A-PC14)") (class "Default")
      (node (ref "C4") (pin "2") (pinfunction "2_2") (pintype "passive"))
      (node (ref "IC4") (pin "3") (pinfunction "PC14_3") (pintype "bidirectional"))
      (node (ref "LSE") (pin "1") (pinfunction "1_1") (pintype "passive"))
    )
    (net (code "88") (name "Net-(IC4A-PC15)") (class "Default")
      (node (ref "C1") (pin "2") (pinfunction "2_2") (pintype "passive"))
      (node (ref "IC4") (pin "4") (pinfunction "PC15_4") (pintype "bidirectional"))
      (node (ref "LSE") (pin "2") (pinfunction "2_2") (pintype "passive"))
    )
    (net (code "89") (name "Net-(IC4A-VCAP1)") (class "Default")
      (node (ref "C17") (pin "2") (pinfunction "2_2") (pintype "passive"))
      (node (ref "IC4") (pin "31") (pinfunction "VCAP1_31") (pintype "power_in"))
    )
    (net (code "90") (name "Net-(IC4A-VCAP2)") (class "Default")
      (node (ref "C18") (pin "2") (pinfunction "2_2") (pintype "passive"))
      (node (ref "IC4") (pin "47") (pinfunction "VCAP2_47") (pintype "power_in"))
    )
    (net (code "91") (name "Net-(IC6-DMI)") (class "Default")
      (node (ref "IC6") (pin "3") (pinfunction "DMI_3") (pintype "bidirectional"))
      (node (ref "X3") (pin "2") (pinfunction "2_2") (pintype "passive"))
    )
    (net (code "92") (name "Net-(IC6-DPI)") (class "Default")
      (node (ref "IC6") (pin "1") (pinfunction "DPI_1") (pintype "bidirectional"))
      (node (ref "X3") (pin "3") (pinfunction "3_3") (pintype "passive"))
    )
    (net (code "93") (name "Net-(IC6-DPO)") (class "Default")
      (node (ref "IC6") (pin "6") (pinfunction "DPO_6") (pintype "bidirectional"))
      (node (ref "IC7") (pin "15") (pinfunction "USBDP_15") (pintype "bidirectional"))
    )
    (net (code "94") (name "Net-(IC7-RXD)") (class "Default")
      (node (ref "IC7") (pin "5") (pinfunction "RXD_5") (pintype "input"))
      (node (ref "IC8") (pin "3") (pinfunction "A2_3") (pintype "bidirectional"))
    )
    (net (code "95") (name "Net-(IC7-TXD)") (class "Default")
      (node (ref "IC7") (pin "1") (pinfunction "TXD_1") (pintype "output"))
      (node (ref "IC8") (pin "2") (pinfunction "A1_2") (pintype "bidirectional"))
    )
    (net (code "96") (name "Net-(Q1-G)") (class "Default")
      (node (ref "Q1") (pin "1") (pinfunction "G_1") (pintype "passive"))
      (node (ref "R13") (pin "1") (pinfunction "1_1") (pintype "passive"))
    )
    (net (code "97") (name "Net-(Q2-G)") (class "Default")
      (node (ref "Q2") (pin "1") (pinfunction "G_1") (pintype "passive"))
      (node (ref "R5") (pin "1") (pinfunction "1_1") (pintype "passive"))
    )
    (net (code "98") (name "Net-(Q3-G)") (class "Default")
      (node (ref "Q3") (pin "1") (pinfunction "G_1") (pintype "passive"))
      (node (ref "R10") (pin "1") (pinfunction "1_1") (pintype "passive"))
    )
    (net (code "99") (name "Net-(Q4-G)") (class "Default")
      (node (ref "Q4") (pin "1") (pinfunction "G_1") (pintype "passive"))
      (node (ref "R12") (pin "1") (pinfunction "1_1") (pintype "passive"))
    )
    (net (code "100") (name "Net-(Q5-G)") (class "Default")
      (node (ref "C25") (pin "2") (pinfunction "2_2") (pintype "passive"))
      (node (ref "Q5") (pin "1") (pinfunction "G_1") (pintype "passive"))
      (node (ref "R24") (pin "1") (pinfunction "1_1") (pintype "passive"))
    )
    (net (code "101") (name "VCC") (class "Default")
      (node (ref "BUTTONS") (pin "1") (pinfunction "1_1") (pintype "passive"))
      (node (ref "C10") (pin "2") (pinfunction "2_2") (pintype "passive"))
      (node (ref "C11") (pin "2") (pinfunction "2_2") (pintype "passive"))
      (node (ref "C12") (pin "2") (pinfunction "2_2") (pintype "passive"))
      (node (ref "C13") (pin "2") (pinfunction "2_2") (pintype "passive"))
      (node (ref "C14") (pin "2") (pinfunction "2_2") (pintype "passive"))
      (node (ref "C3") (pin "2") (pinfunction "2_2") (pintype "passive"))
      (node (ref "C8") (pin "2") (pinfunction "2_2") (pintype "passive"))
      (node (ref "C9") (pin "2") (pinfunction "2_2") (pintype "passive"))
      (node (ref "D1") (pin "P$2") (pinfunction "C_P$2") (pintype "passive"))
      (node (ref "IC10") (pin "2") (pinfunction "VOUT_2") (pintype "output"))
      (node (ref "IC2") (pin "1") (pinfunction "VDD1_1") (pintype "bidirectional"))
      (node (ref "IC3") (pin "6") (pinfunction "VCC_6") (pintype "power_in"))
      (node (ref "IC4") (pin "1") (pinfunction "VBAT_1") (pintype "power_in"))
      (node (ref "IC4") (pin "13") (pinfunction "VDDA_13") (pintype "power_in"))
      (node (ref "IC4") (pin "19") (pinfunction "VDD_19") (pintype "power_in"))
      (node (ref "IC4") (pin "32") (pinfunction "VDD_32") (pintype "power_in"))
      (node (ref "IC4") (pin "48") (pinfunction "VDD_48") (pintype "power_in"))
      (node (ref "IC4") (pin "64") (pinfunction "VDD_64") (pintype "power_in"))
      (node (ref "IC8") (pin "8") (pinfunction "VDD2_8") (pintype "bidirectional"))
      (node (ref "R1") (pin "2") (pinfunction "2_2") (pintype "passive"))
      (node (ref "R14") (pin "1") (pinfunction "1_1") (pintype "passive"))
      (node (ref "R15") (pin "1") (pinfunction "1_1") (pintype "passive"))
      (node (ref "R17") (pin "1") (pinfunction "1_1") (pintype "passive"))
      (node (ref "R19") (pin "1") (pinfunction "1_1") (pintype "passive"))
      (node (ref "R2") (pin "2") (pinfunction "2_2") (pintype "passive"))
      (node (ref "R21") (pin "1") (pinfunction "1_1") (pintype "passive"))
      (node (ref "SWD") (pin "1") (pinfunction "1_1") (pintype "passive"))
    )
    (net (code "102") (name "unconnected-(ENCODERS-Pad1)") (class "Default")
      (node (ref "ENCODERS") (pin "1") (pinfunction "1_1") (pintype "passive"))
    )
    (net (code "103") (name "unconnected-(ENCODERS-Pad10)") (class "Default")
      (node (ref "ENCODERS") (pin "10") (pinfunction "10_10") (pintype "passive"))
    )
    (net (code "104") (name "unconnected-(I2C2-Pad2)") (class "Default")
      (node (ref "I2C2") (pin "2") (pinfunction "2_2") (pintype "passive"))
    )
    (net (code "105") (name "unconnected-(I2C2-Pad4)") (class "Default")
      (node (ref "I2C2") (pin "4") (pinfunction "4_4") (pintype "passive"))
    )
    (net (code "106") (name "unconnected-(I2C2-Pad6)") (class "Default")
      (node (ref "I2C2") (pin "6") (pinfunction "6_6") (pintype "passive"))
    )
    (net (code "107") (name "unconnected-(IC2-B5-Pad11)") (class "Default")
      (node (ref "IC2") (pin "11") (pinfunction "B5_11") (pintype "bidirectional"))
    )
    (net (code "108") (name "unconnected-(IC2-B6-Pad10)") (class "Default")
      (node (ref "IC2") (pin "10") (pinfunction "B6_10") (pintype "bidirectional"))
    )
    (net (code "109") (name "unconnected-(IC7-3V3OUT-Pad17)") (class "Default")
      (node (ref "IC7") (pin "17") (pinfunction "3V3OUT_17") (pintype "output"))
    )
    (net (code "110") (name "unconnected-(IC7-OSCI-Pad27)") (class "Default")
      (node (ref "IC7") (pin "27") (pinfunction "OSCI_27") (pintype "input"))
    )
    (net (code "111") (name "unconnected-(IC7-OSCO-Pad28)") (class "Default")
      (node (ref "IC7") (pin "28") (pinfunction "OSCO_28") (pintype "output"))
    )
    (net (code "112") (name "unconnected-(IC7-~{CTS}-Pad11)") (class "Default")
      (node (ref "IC7") (pin "11") (pinfunction "~{CTS}_11") (pintype "input"))
    )
    (net (code "113") (name "unconnected-(IC7-~{DCD}-Pad10)") (class "Default")
      (node (ref "IC7") (pin "10") (pinfunction "~{DCD}_10") (pintype "input"))
    )
    (net (code "114") (name "unconnected-(IC7-~{DSR}-Pad9)") (class "Default")
      (node (ref "IC7") (pin "9") (pinfunction "~{DSR}_9") (pintype "input"))
    )
    (net (code "115") (name "unconnected-(IC7-~{DTR}-Pad2)") (class "Default")
      (node (ref "IC7") (pin "2") (pinfunction "~{DTR}_2") (pintype "output"))
    )
    (net (code "116") (name "unconnected-(IC7-~{RESET}-Pad19)") (class "Default")
      (node (ref "IC7") (pin "19") (pinfunction "~{RESET}_19") (pintype "input"))
    )
    (net (code "117") (name "unconnected-(IC7-~{RI}-Pad6)") (class "Default")
      (node (ref "IC7") (pin "6") (pinfunction "~{RI}_6") (pintype "input"))
    )
    (net (code "118") (name "unconnected-(IC7-~{RTS}-Pad3)") (class "Default")
      (node (ref "IC7") (pin "3") (pinfunction "~{RTS}_3") (pintype "output"))
    )
    (net (code "119") (name "unconnected-(LSP1-PadMP)") (class "Default")
      (node (ref "LSP1") (pin "MP") (pinfunction "MP_MP") (pintype "passive"))
    )
    (net (code "120") (name "unconnected-(LSP2-PadMP)") (class "Default")
      (node (ref "LSP2") (pin "MP") (pinfunction "MP_MP") (pintype "passive"))
    )
    (net (code "121") (name "unconnected-(LSP3-PadMP)") (class "Default")
      (node (ref "LSP3") (pin "MP") (pinfunction "MP_MP") (pintype "passive"))
    )
    (net (code "122") (name "unconnected-(LSP4-PadMP)") (class "Default")
      (node (ref "LSP4") (pin "MP") (pinfunction "MP_MP") (pintype "passive"))
    )
    (net (code "123") (name "unconnected-(SWD-Pad6)") (class "Default")
      (node (ref "SWD") (pin "6") (pinfunction "6_6") (pintype "passive"))
    )
    (net (code "124") (name "unconnected-(X3-Pad4)") (class "Default")
      (node (ref "X3") (pin "4") (pinfunction "4_4") (pintype "passive"))
    )
  )
)
